# sdi-master.net
KiCad netlist of a schematic drawn in EAGLE
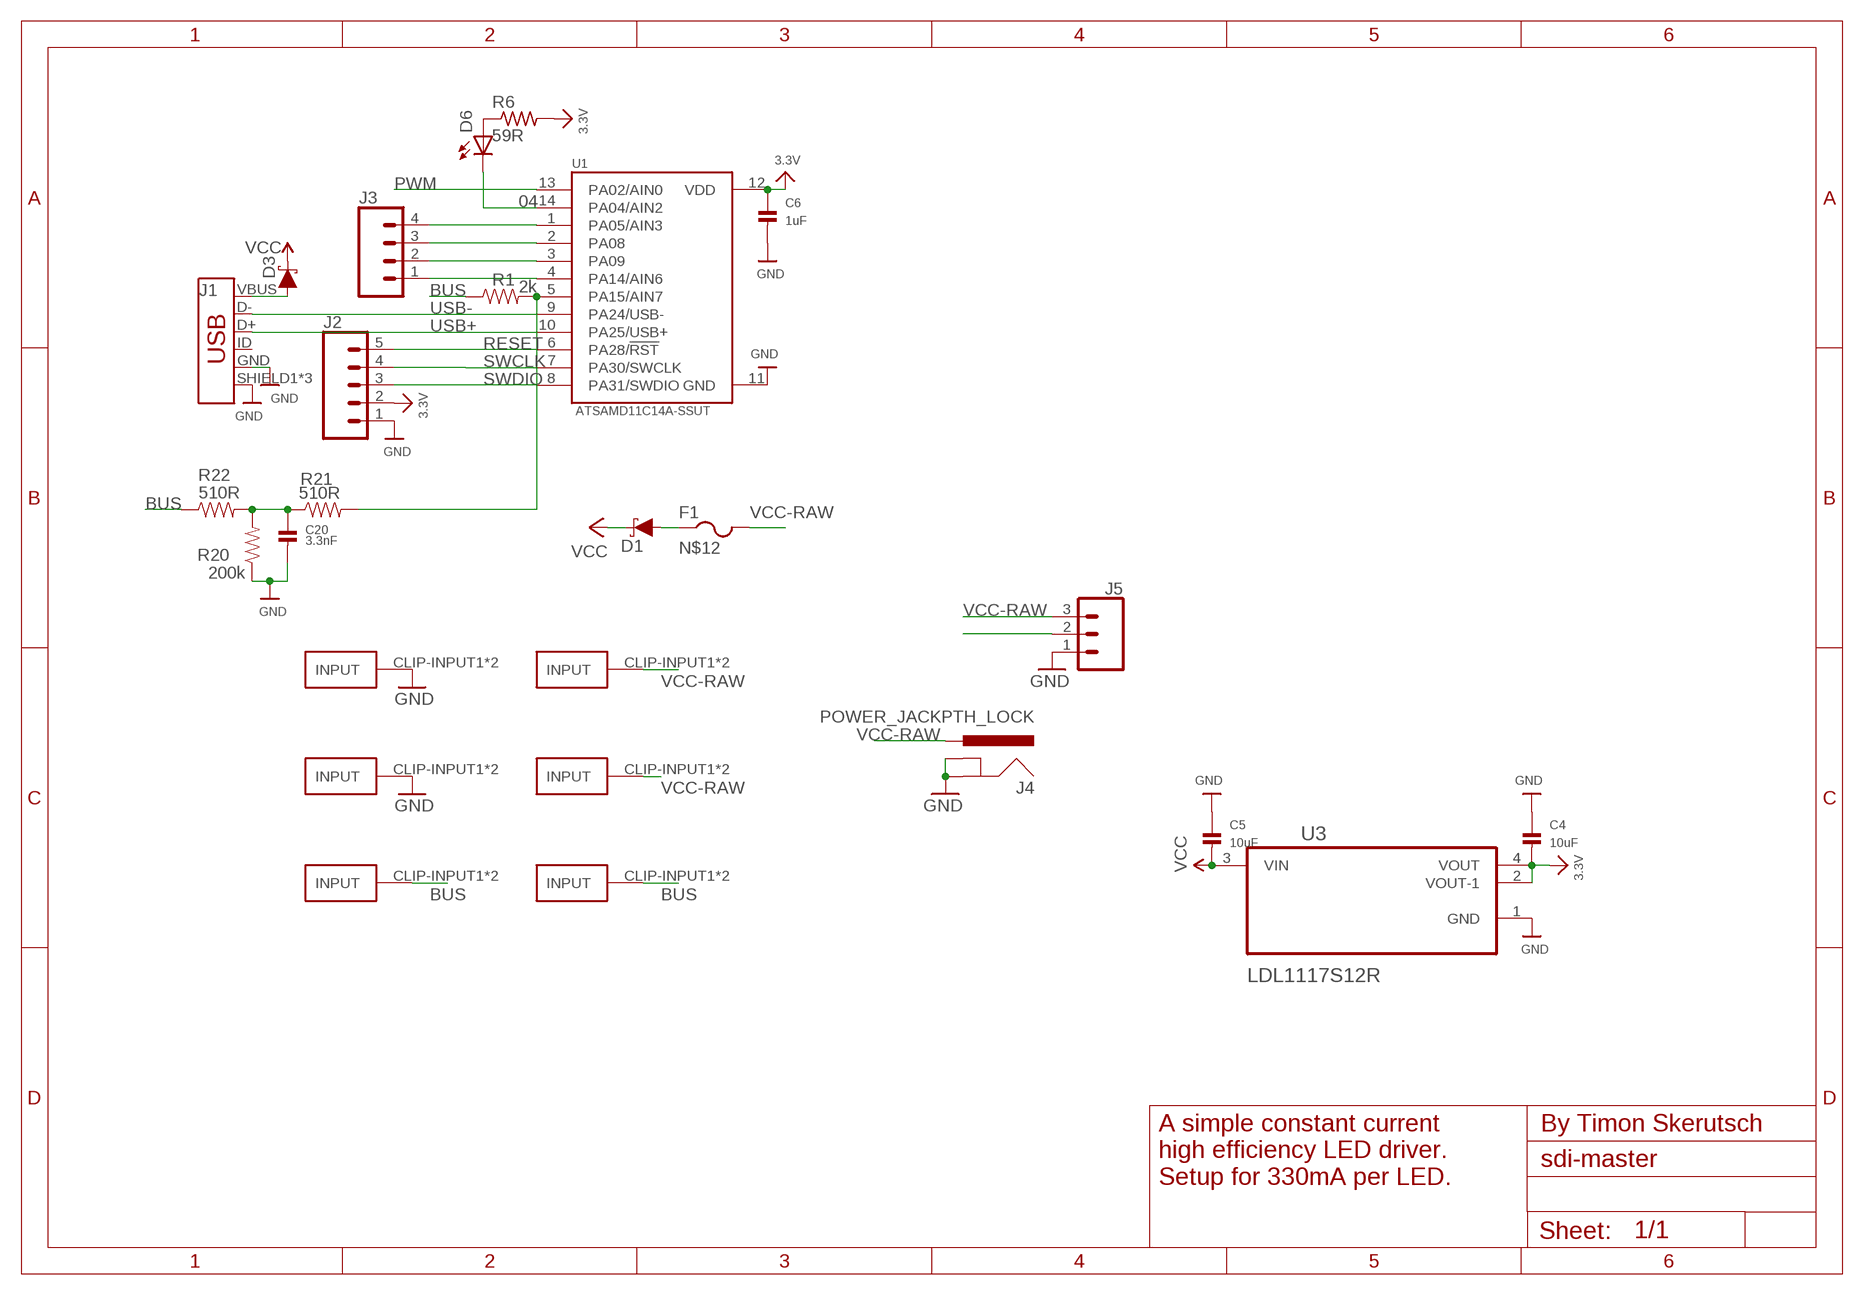
[diagram p0: schematic, sheet 1]

(export (version "E")
  (design (tool "Eeschema 10.0.6"))
  (components
    (comp (ref "C4")
      (value "10uF")
      (footprint "eagle-import:0805")
      (libsource (lib "eagle-import") (part "CAP_CERAMIC0805"))
    )
    (comp (ref "C5")
      (value "10uF")
      (footprint "eagle-import:0603")
      (libsource (lib "eagle-import") (part "CAP_CERAMIC0603"))
    )
    (comp (ref "C6")
      (value "1uF")
      (footprint "eagle-import:0603")
      (libsource (lib "eagle-import") (part "CAP_CERAMIC0603"))
    )
    (comp (ref "C20")
      (value "3.3nF")
      (footprint "eagle-import:0603")
      (libsource (lib "eagle-import") (part "CAP_CERAMIC0603"))
    )
    (comp (ref "D1")
      (value "3A/40V/500mV")
      (footprint "eagle-import:SMA-DIODE")
      (libsource (lib "eagle-import") (part "DIODE-SCHOTTKY-B340A"))
    )
    (comp (ref "D3")
      (value "3A/40V/500mV")
      (footprint "eagle-import:SMA-DIODE")
      (libsource (lib "eagle-import") (part "DIODE-SCHOTTKY-B340A"))
    )
    (comp (ref "D6")
      (value "LEDCHIPLED_0805")
      (footprint "eagle-import:CHIPLED_0805")
      (libsource (lib "eagle-import") (part "LEDCHIPLED_0805"))
    )
    (comp (ref "F1")
      (value "TLC-MSMD110/24")
      (footprint "eagle-import:1812")
      (libsource (lib "eagle-import") (part "PTCFUSE-1812"))
    )
    (comp (ref "GND-CLIP")
      (value "FUSE-HOLDER-5X20MM")
      (footprint "eagle-import:FUSE-HOLDER-5X20MM")
      (libsource (lib "eagle-import") (part "FUSE-HOLDER-5X20MM"))
    )
    (comp (ref "GND-CLIP3")
      (value "FUSE-HOLDER-5X20MM")
      (footprint "eagle-import:FUSE-HOLDER-5X20MM")
      (libsource (lib "eagle-import") (part "FUSE-HOLDER-5X20MM"))
    )
    (comp (ref "J1")
      (value "USB_MICRO-B_FEMALE-SMT")
      (footprint "eagle-import:USB-B-MICRO-SMD")
      (libsource (lib "eagle-import") (part "USB_MICRO-B_FEMALE-SMT"))
    )
    (comp (ref "J2")
      (value "CONN_05")
      (footprint "eagle-import:1X05")
      (libsource (lib "eagle-import") (part "CONN_05"))
    )
    (comp (ref "J3")
      (value "CONN_04PTH")
      (footprint "eagle-import:1X04")
      (libsource (lib "eagle-import") (part "CONN_04PTH"))
    )
    (comp (ref "J4")
      (value "POWER_JACKPTH_LOCK")
      (footprint "eagle-import:POWER_JACK_PTH_LOCK")
      (libsource (lib "eagle-import") (part "POWER_JACKPTH_LOCK"))
    )
    (comp (ref "J5")
      (value "CONN_03SCREW-NS")
      (footprint "eagle-import:SCREWTERMINAL-3.5MM-3-NS")
      (libsource (lib "eagle-import") (part "CONN_03SCREW-NS"))
    )
    (comp (ref "PWM-CLIP")
      (value "FUSE-HOLDER-5X20MM")
      (footprint "eagle-import:FUSE-HOLDER-5X20MM")
      (libsource (lib "eagle-import") (part "FUSE-HOLDER-5X20MM"))
    )
    (comp (ref "PWM-CLIP1")
      (value "FUSE-HOLDER-5X20MM")
      (footprint "eagle-import:FUSE-HOLDER-5X20MM")
      (libsource (lib "eagle-import") (part "FUSE-HOLDER-5X20MM"))
    )
    (comp (ref "R1")
      (value "2k")
      (footprint "eagle-import:1206")
      (libsource (lib "eagle-import") (part "RESISTOR1206"))
    )
    (comp (ref "R6")
      (value "59R")
      (footprint "eagle-import:R0805")
      (libsource (lib "eagle-import") (part "R-US_R0805"))
    )
    (comp (ref "R20")
      (value "200k")
      (footprint "eagle-import:1206")
      (libsource (lib "eagle-import") (part "RESISTOR1206"))
    )
    (comp (ref "R21")
      (value "510R")
      (footprint "eagle-import:1206")
      (libsource (lib "eagle-import") (part "RESISTOR1206"))
    )
    (comp (ref "R22")
      (value "510R")
      (footprint "eagle-import:1206")
      (libsource (lib "eagle-import") (part "RESISTOR1206"))
    )
    (comp (ref "U1")
      (value "ATSAMD11C14A-SSUT")
      (footprint "eagle-import:SOIC127P600X160-14N")
      (fields (field (name "MF") "Microchip"))
      (libsource (lib "eagle-import") (part "ATSAMD11C14A-SSUT"))
    )
    (comp (ref "U3")
      (value "LDL1117S12R")
      (footprint "eagle-import:SOT230P700X180-4N")
      (fields (field (name "MF") "STMicroelectronics"))
      (libsource (lib "eagle-import") (part "LDL1117S12R"))
    )
    (comp (ref "VCC-CLIP")
      (value "FUSE-HOLDER-5X20MM")
      (footprint "eagle-import:FUSE-HOLDER-5X20MM")
      (libsource (lib "eagle-import") (part "FUSE-HOLDER-5X20MM"))
    )
    (comp (ref "VCC-CLIP3")
      (value "FUSE-HOLDER-5X20MM")
      (footprint "eagle-import:FUSE-HOLDER-5X20MM")
      (libsource (lib "eagle-import") (part "FUSE-HOLDER-5X20MM"))
    )
  )
  (nets
    (net (code "1") (name "/04") (class "Default")
      (node (ref "D6") (pin "C") (pinfunction "C_C") (pintype "passive"))
      (node (ref "U1") (pin "14") (pinfunction "PA04/AIN2_14") (pintype "bidirectional"))
    )
    (net (code "2") (name "/BUS") (class "Default")
      (node (ref "J5") (pin "2") (pinfunction "2_2") (pintype "passive"))
      (node (ref "PWM-CLIP") (pin "CLIP-INPUT1") (pinfunction "INPUT_CLIP-INPUT1") (pintype "bidirectional"))
      (node (ref "PWM-CLIP") (pin "CLIP-INPUT2") (pinfunction "INPUT_CLIP-INPUT2") (pintype "bidirectional"))
      (node (ref "PWM-CLIP1") (pin "CLIP-INPUT1") (pinfunction "INPUT_CLIP-INPUT1") (pintype "bidirectional"))
      (node (ref "PWM-CLIP1") (pin "CLIP-INPUT2") (pinfunction "INPUT_CLIP-INPUT2") (pintype "bidirectional"))
      (node (ref "R1") (pin "1") (pinfunction "1_1") (pintype "passive"))
      (node (ref "R22") (pin "1") (pinfunction "1_1") (pintype "passive"))
    )
    (net (code "3") (name "/N$12") (class "Default")
      (node (ref "D1") (pin "A") (pinfunction "A_A") (pintype "passive"))
      (node (ref "F1") (pin "1") (pinfunction "1_1") (pintype "passive"))
    )
    (net (code "4") (name "/PWM") (class "Default")
      (node (ref "U1") (pin "13") (pinfunction "PA02/AIN0_13") (pintype "bidirectional"))
    )
    (net (code "5") (name "/RESET") (class "Default")
      (node (ref "J2") (pin "5") (pinfunction "5_5") (pintype "passive"))
      (node (ref "U1") (pin "6") (pinfunction "PA28/~{RST}_6") (pintype "bidirectional"))
    )
    (net (code "6") (name "/SWCLK") (class "Default")
      (node (ref "J2") (pin "4") (pinfunction "4_4") (pintype "passive"))
      (node (ref "U1") (pin "7") (pinfunction "PA30/SWCLK_7") (pintype "bidirectional"))
    )
    (net (code "7") (name "/SWDIO") (class "Default")
      (node (ref "J2") (pin "3") (pinfunction "3_3") (pintype "passive"))
      (node (ref "U1") (pin "8") (pinfunction "PA31/SWDIO_8") (pintype "bidirectional"))
    )
    (net (code "8") (name "/USB+") (class "Default")
      (node (ref "J1") (pin "D+") (pinfunction "D+_D+") (pintype "bidirectional"))
      (node (ref "U1") (pin "10") (pinfunction "PA25/USB+_10") (pintype "bidirectional"))
    )
    (net (code "9") (name "/USB-") (class "Default")
      (node (ref "J1") (pin "D-") (pinfunction "D-_D-") (pintype "bidirectional"))
      (node (ref "U1") (pin "9") (pinfunction "PA24/USB-_9") (pintype "bidirectional"))
    )
    (net (code "10") (name "/VCC-RAW") (class "Default")
      (node (ref "F1") (pin "2") (pinfunction "2_2") (pintype "passive"))
      (node (ref "J4") (pin "PWR") (pinfunction "PWR_PWR") (pintype "bidirectional"))
      (node (ref "J5") (pin "3") (pinfunction "3_3") (pintype "passive"))
      (node (ref "VCC-CLIP") (pin "CLIP-INPUT1") (pinfunction "INPUT_CLIP-INPUT1") (pintype "bidirectional"))
      (node (ref "VCC-CLIP") (pin "CLIP-INPUT2") (pinfunction "INPUT_CLIP-INPUT2") (pintype "bidirectional"))
      (node (ref "VCC-CLIP3") (pin "CLIP-INPUT1") (pinfunction "INPUT_CLIP-INPUT1") (pintype "bidirectional"))
      (node (ref "VCC-CLIP3") (pin "CLIP-INPUT2") (pinfunction "INPUT_CLIP-INPUT2") (pintype "bidirectional"))
    )
    (net (code "11") (name "3.3V") (class "Default")
      (node (ref "C4") (pin "2") (pinfunction "P$2_2") (pintype "passive"))
      (node (ref "C6") (pin "1") (pinfunction "P$1_1") (pintype "passive"))
      (node (ref "J2") (pin "2") (pinfunction "2_2") (pintype "passive"))
      (node (ref "R6") (pin "2") (pinfunction "2_2") (pintype "passive"))
      (node (ref "U1") (pin "12") (pinfunction "VDD_12") (pintype "power_in"))
      (node (ref "U3") (pin "2") (pinfunction "VOUT-1_2") (pintype "output"))
      (node (ref "U3") (pin "4") (pinfunction "VOUT_4") (pintype "output"))
    )
    (net (code "12") (name "GND") (class "Default")
      (node (ref "C20") (pin "2") (pinfunction "P$2_2") (pintype "passive"))
      (node (ref "C4") (pin "1") (pinfunction "P$1_1") (pintype "passive"))
      (node (ref "C5") (pin "1") (pinfunction "P$1_1") (pintype "passive"))
      (node (ref "C6") (pin "2") (pinfunction "P$2_2") (pintype "passive"))
      (node (ref "GND-CLIP") (pin "CLIP-INPUT1") (pinfunction "INPUT_CLIP-INPUT1") (pintype "bidirectional"))
      (node (ref "GND-CLIP") (pin "CLIP-INPUT2") (pinfunction "INPUT_CLIP-INPUT2") (pintype "bidirectional"))
      (node (ref "GND-CLIP3") (pin "CLIP-INPUT1") (pinfunction "INPUT_CLIP-INPUT1") (pintype "bidirectional"))
      (node (ref "GND-CLIP3") (pin "CLIP-INPUT2") (pinfunction "INPUT_CLIP-INPUT2") (pintype "bidirectional"))
      (node (ref "J1") (pin "GND") (pinfunction "GND_GND") (pintype "power_in"))
      (node (ref "J1") (pin "SHIELD1") (pinfunction "SHIELD_SHIELD1") (pintype "bidirectional"))
      (node (ref "J1") (pin "SHIELD2") (pinfunction "SHIELD_SHIELD2") (pintype "bidirectional"))
      (node (ref "J1") (pin "SHIELD3") (pinfunction "SHIELD_SHIELD3") (pintype "bidirectional"))
      (node (ref "J2") (pin "1") (pinfunction "1_1") (pintype "passive"))
      (node (ref "J4") (pin "GND") (pinfunction "GND_GND") (pintype "bidirectional"))
      (node (ref "J4") (pin "GNDBREAK") (pinfunction "GNDBREAK_GNDBREAK") (pintype "bidirectional"))
      (node (ref "J5") (pin "1") (pinfunction "1_1") (pintype "passive"))
      (node (ref "R20") (pin "1") (pinfunction "1_1") (pintype "passive"))
      (node (ref "U1") (pin "11") (pinfunction "GND_11") (pintype "power_in"))
      (node (ref "U3") (pin "1") (pinfunction "GND_1") (pintype "power_in"))
    )
    (net (code "13") (name "Net-(C20-P$1)") (class "Default")
      (node (ref "C20") (pin "1") (pinfunction "P$1_1") (pintype "passive"))
      (node (ref "R20") (pin "2") (pinfunction "2_2") (pintype "passive"))
      (node (ref "R21") (pin "1") (pinfunction "1_1") (pintype "passive"))
      (node (ref "R22") (pin "2") (pinfunction "2_2") (pintype "passive"))
    )
    (net (code "14") (name "Net-(D3-PadA)") (class "Default")
      (node (ref "D3") (pin "A") (pinfunction "A_A") (pintype "passive"))
      (node (ref "J1") (pin "VBUS") (pinfunction "VBUS_VBUS") (pintype "power_in"))
    )
    (net (code "15") (name "Net-(D6-PadA)") (class "Default")
      (node (ref "D6") (pin "A") (pinfunction "A_A") (pintype "passive"))
      (node (ref "R6") (pin "1") (pinfunction "1_1") (pintype "passive"))
    )
    (net (code "16") (name "Net-(U1-PA05{slash}AIN3)") (class "Default")
      (node (ref "J3") (pin "4") (pinfunction "4_4") (pintype "passive"))
      (node (ref "U1") (pin "1") (pinfunction "PA05/AIN3_1") (pintype "bidirectional"))
    )
    (net (code "17") (name "Net-(U1-PA08)") (class "Default")
      (node (ref "J3") (pin "3") (pinfunction "3_3") (pintype "passive"))
      (node (ref "U1") (pin "2") (pinfunction "PA08_2") (pintype "bidirectional"))
    )
    (net (code "18") (name "Net-(U1-PA09)") (class "Default")
      (node (ref "J3") (pin "2") (pinfunction "2_2") (pintype "passive"))
      (node (ref "U1") (pin "3") (pinfunction "PA09_3") (pintype "bidirectional"))
    )
    (net (code "19") (name "Net-(U1-PA14{slash}AIN6)") (class "Default")
      (node (ref "J3") (pin "1") (pinfunction "1_1") (pintype "passive"))
      (node (ref "U1") (pin "4") (pinfunction "PA14/AIN6_4") (pintype "bidirectional"))
    )
    (net (code "20") (name "Net-(U1-PA15{slash}AIN7)") (class "Default")
      (node (ref "R1") (pin "2") (pinfunction "2_2") (pintype "passive"))
      (node (ref "R21") (pin "2") (pinfunction "2_2") (pintype "passive"))
      (node (ref "U1") (pin "5") (pinfunction "PA15/AIN7_5") (pintype "bidirectional"))
    )
    (net (code "21") (name "VCC") (class "Default")
      (node (ref "C5") (pin "2") (pinfunction "P$2_2") (pintype "passive"))
      (node (ref "D1") (pin "C") (pinfunction "C_C") (pintype "passive"))
      (node (ref "D3") (pin "C") (pinfunction "C_C") (pintype "passive"))
      (node (ref "U3") (pin "3") (pinfunction "VIN_3") (pintype "input"))
    )
    (net (code "22") (name "unconnected-(J1-PadID)") (class "Default")
      (node (ref "J1") (pin "ID") (pinfunction "ID_ID") (pintype "bidirectional"))
    )
  )
)
